# v22_50_maker.net
KiCad netlist of a schematic drawn in EAGLE
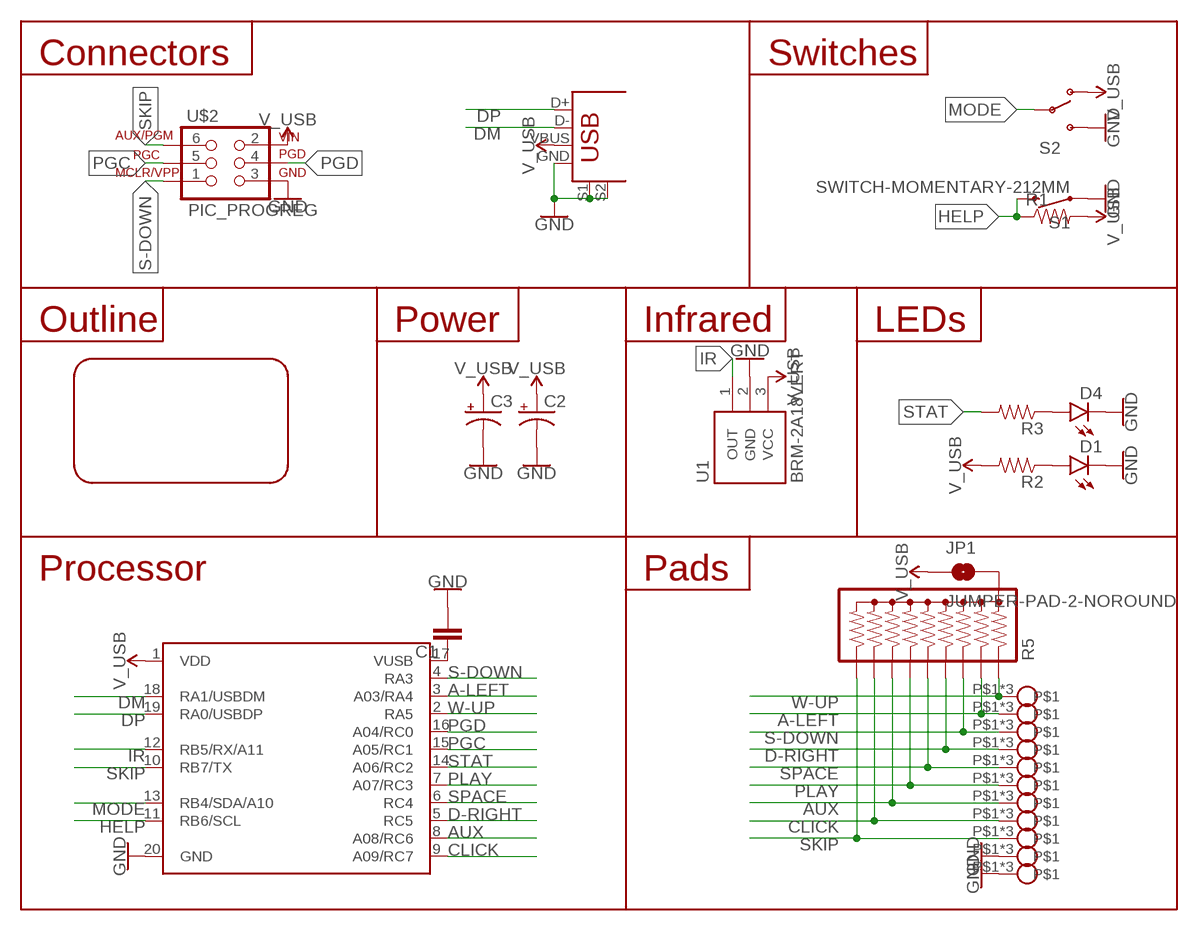
[diagram p0: schematic, sheet 1]

(export (version "E")
  (design (tool "Eeschema 10.0.6"))
  (components
    (comp (ref "C1")
      (value "CAPPTH")
      (footprint "eagle-import:CAP-PTH-SMALL")
      (libsource (lib "eagle-import") (part "CAPPTH"))
    )
    (comp (ref "C2")
      (value "CAP_POLPTH2")
      (footprint "eagle-import:CPOL-RADIAL-10UF-25V")
      (libsource (lib "eagle-import") (part "CAP_POLPTH2"))
    )
    (comp (ref "C3")
      (value "CAP_POLPTH1")
      (footprint "eagle-import:CPOL-RADIAL-100UF-25V")
      (libsource (lib "eagle-import") (part "CAP_POLPTH1"))
    )
    (comp (ref "D1")
      (value "LED3MM")
      (footprint "eagle-import:LED3MM")
      (libsource (lib "eagle-import") (part "LED3MM"))
    )
    (comp (ref "D4")
      (value "LED3MM")
      (footprint "eagle-import:LED3MM")
      (libsource (lib "eagle-import") (part "LED3MM"))
    )
    (comp (ref "JP1")
      (value "JUMPER-PAD-2-NOROUND")
      (footprint "eagle-import:PAD-JUMPER-2-NO_YES_SILK_ROUND")
      (libsource (lib "eagle-import") (part "JUMPER-PAD-2-NOROUND"))
    )
    (comp (ref "R1")
      (value "RESISTORAXIAL-0.3")
      (footprint "eagle-import:AXIAL-0.3")
      (libsource (lib "eagle-import") (part "RESISTORAXIAL-0.3"))
    )
    (comp (ref "R2")
      (value "RESISTORAXIAL-0.3")
      (footprint "eagle-import:AXIAL-0.3")
      (libsource (lib "eagle-import") (part "RESISTORAXIAL-0.3"))
    )
    (comp (ref "R3")
      (value "RESISTORAXIAL-0.3")
      (footprint "eagle-import:AXIAL-0.3")
      (libsource (lib "eagle-import") (part "RESISTORAXIAL-0.3"))
    )
    (comp (ref "R5")
      (value "RPACK-BUSSED-9ROUND")
      (footprint "eagle-import:RPACK-SIP-PTH-9")
      (libsource (lib "eagle-import") (part "RPACK-BUSSED-9ROUND"))
    )
    (comp (ref "S1")
      (value "SWITCH-MOMENTARY-212MM")
      (footprint "eagle-import:TACTILE-PTH-12MM")
      (libsource (lib "eagle-import") (part "SWITCH-MOMENTARY-212MM"))
    )
    (comp (ref "S2")
      (value "SWITCH-SPDTPTH")
      (footprint "eagle-import:SWITCH-SPDT")
      (libsource (lib "eagle-import") (part "SWITCH-SPDTPTH"))
    )
    (comp (ref "U$1")
      (value "PIC16F1459-I/MLDIL")
      (footprint "eagle-import:DIL20")
      (libsource (lib "eagle-import") (part "PIC16F1459-I/MLDIL"))
    )
    (comp (ref "U$2")
      (value "PIC_PROGREG")
      (footprint "eagle-import:1X06")
      (libsource (lib "eagle-import") (part "PIC_PROGREG"))
    )
    (comp (ref "U$3")
      (value "USB+SHIELD")
      (footprint "eagle-import:USB-B-PTH")
      (libsource (lib "eagle-import") (part "USB+SHIELD"))
    )
    (comp (ref "U$4")
      (value "ALLIGATOR")
      (footprint "eagle-import:ALLIGATOR_CLIP_CONNECTOR")
      (libsource (lib "eagle-import") (part "ALLIGATOR"))
    )
    (comp (ref "U$5")
      (value "ALLIGATOR")
      (footprint "eagle-import:ALLIGATOR_CLIP_CONNECTOR")
      (libsource (lib "eagle-import") (part "ALLIGATOR"))
    )
    (comp (ref "U$6")
      (value "ALLIGATOR")
      (footprint "eagle-import:ALLIGATOR_CLIP_CONNECTOR")
      (libsource (lib "eagle-import") (part "ALLIGATOR"))
    )
    (comp (ref "U$7")
      (value "ALLIGATOR")
      (footprint "eagle-import:ALLIGATOR_CLIP_CONNECTOR")
      (libsource (lib "eagle-import") (part "ALLIGATOR"))
    )
    (comp (ref "U$8")
      (value "ALLIGATOR")
      (footprint "eagle-import:ALLIGATOR_CLIP_CONNECTOR")
      (libsource (lib "eagle-import") (part "ALLIGATOR"))
    )
    (comp (ref "U$9")
      (value "ALLIGATOR")
      (footprint "eagle-import:ALLIGATOR_CLIP_CONNECTOR")
      (libsource (lib "eagle-import") (part "ALLIGATOR"))
    )
    (comp (ref "U$10")
      (value "ALLIGATOR")
      (footprint "eagle-import:ALLIGATOR_CLIP_CONNECTOR")
      (libsource (lib "eagle-import") (part "ALLIGATOR"))
    )
    (comp (ref "U$11")
      (value "ALLIGATOR")
      (footprint "eagle-import:ALLIGATOR_CLIP_CONNECTOR")
      (libsource (lib "eagle-import") (part "ALLIGATOR"))
    )
    (comp (ref "U$12")
      (value "ALLIGATOR")
      (footprint "eagle-import:ALLIGATOR_CLIP_CONNECTOR")
      (libsource (lib "eagle-import") (part "ALLIGATOR"))
    )
    (comp (ref "U$13")
      (value "ALLIGATOR")
      (footprint "eagle-import:ALLIGATOR_CLIP_CONNECTOR")
      (libsource (lib "eagle-import") (part "ALLIGATOR"))
    )
    (comp (ref "U$14")
      (value "ALLIGATOR")
      (footprint "eagle-import:ALLIGATOR_CLIP_CONNECTOR")
      (libsource (lib "eagle-import") (part "ALLIGATOR"))
    )
    (comp (ref "U$15")
      (value "CARD_STANDARD50MM")
      (footprint "eagle-import:IEC-7810_ID-1_50MM")
      (libsource (lib "eagle-import") (part "CARD_STANDARD50MM"))
    )
    (comp (ref "U1")
      (value "BRM-2A18VERT")
      (footprint "eagle-import:BRM-2508_VERT")
      (libsource (lib "eagle-import") (part "BRM-2A18VERT"))
    )
  )
  (nets
    (net (code "1") (name "/A-LEFT") (class "Default")
      (node (ref "R5") (pin "P$3") (pinfunction "3_P$3") (pintype "passive"))
      (node (ref "U$1") (pin "3") (pinfunction "A03/RA4_3") (pintype "bidirectional"))
      (node (ref "U$4") (pin "P$1") (pinfunction "P$1_P$1") (pintype "bidirectional"))
      (node (ref "U$4") (pin "P$2") (pinfunction "P$1_P$2") (pintype "bidirectional"))
      (node (ref "U$4") (pin "P$3") (pinfunction "P$1_P$3") (pintype "bidirectional"))
    )
    (net (code "2") (name "/AUX") (class "Default")
      (node (ref "R5") (pin "P$8") (pinfunction "8_P$8") (pintype "passive"))
      (node (ref "U$1") (pin "8") (pinfunction "A08/RC6_8") (pintype "bidirectional"))
      (node (ref "U$10") (pin "P$1") (pinfunction "P$1_P$1") (pintype "bidirectional"))
      (node (ref "U$10") (pin "P$2") (pinfunction "P$1_P$2") (pintype "bidirectional"))
      (node (ref "U$10") (pin "P$3") (pinfunction "P$1_P$3") (pintype "bidirectional"))
    )
    (net (code "3") (name "/CLICK") (class "Default")
      (node (ref "R5") (pin "P$9") (pinfunction "9_P$9") (pintype "passive"))
      (node (ref "U$1") (pin "9") (pinfunction "A09/RC7_9") (pintype "bidirectional"))
      (node (ref "U$11") (pin "P$1") (pinfunction "P$1_P$1") (pintype "bidirectional"))
      (node (ref "U$11") (pin "P$2") (pinfunction "P$1_P$2") (pintype "bidirectional"))
      (node (ref "U$11") (pin "P$3") (pinfunction "P$1_P$3") (pintype "bidirectional"))
    )
    (net (code "4") (name "/D-RIGHT") (class "Default")
      (node (ref "R5") (pin "P$5") (pinfunction "5_P$5") (pintype "passive"))
      (node (ref "U$1") (pin "5") (pinfunction "RC5_5") (pintype "bidirectional"))
      (node (ref "U$5") (pin "P$1") (pinfunction "P$1_P$1") (pintype "bidirectional"))
      (node (ref "U$5") (pin "P$2") (pinfunction "P$1_P$2") (pintype "bidirectional"))
      (node (ref "U$5") (pin "P$3") (pinfunction "P$1_P$3") (pintype "bidirectional"))
    )
    (net (code "5") (name "/DM") (class "Default")
      (node (ref "U$1") (pin "18") (pinfunction "RA1/USBDM_18") (pintype "bidirectional"))
      (node (ref "U$3") (pin "D-") (pinfunction "D-_D-") (pintype "bidirectional"))
    )
    (net (code "6") (name "/DP") (class "Default")
      (node (ref "U$1") (pin "19") (pinfunction "RA0/USBDP_19") (pintype "bidirectional"))
      (node (ref "U$3") (pin "D+") (pinfunction "D+_D+") (pintype "bidirectional"))
    )
    (net (code "7") (name "/PLAY") (class "Default")
      (node (ref "R5") (pin "P$7") (pinfunction "7_P$7") (pintype "passive"))
      (node (ref "U$1") (pin "7") (pinfunction "A07/RC3_7") (pintype "bidirectional"))
      (node (ref "U$9") (pin "P$1") (pinfunction "P$1_P$1") (pintype "bidirectional"))
      (node (ref "U$9") (pin "P$2") (pinfunction "P$1_P$2") (pintype "bidirectional"))
      (node (ref "U$9") (pin "P$3") (pinfunction "P$1_P$3") (pintype "bidirectional"))
    )
    (net (code "8") (name "/SPACE") (class "Default")
      (node (ref "R5") (pin "P$6") (pinfunction "6_P$6") (pintype "passive"))
      (node (ref "U$1") (pin "6") (pinfunction "RC4_6") (pintype "bidirectional"))
      (node (ref "U$8") (pin "P$1") (pinfunction "P$1_P$1") (pintype "bidirectional"))
      (node (ref "U$8") (pin "P$2") (pinfunction "P$1_P$2") (pintype "bidirectional"))
      (node (ref "U$8") (pin "P$3") (pinfunction "P$1_P$3") (pintype "bidirectional"))
    )
    (net (code "9") (name "/W-UP") (class "Default")
      (node (ref "R5") (pin "P$2") (pinfunction "2_P$2") (pintype "passive"))
      (node (ref "U$1") (pin "2") (pinfunction "RA5_2") (pintype "bidirectional"))
      (node (ref "U$6") (pin "P$1") (pinfunction "P$1_P$1") (pintype "bidirectional"))
      (node (ref "U$6") (pin "P$2") (pinfunction "P$1_P$2") (pintype "bidirectional"))
      (node (ref "U$6") (pin "P$3") (pinfunction "P$1_P$3") (pintype "bidirectional"))
    )
    (net (code "10") (name "GND") (class "Default")
      (node (ref "C1") (pin "2") (pinfunction "2_2") (pintype "passive"))
      (node (ref "C2") (pin "2") (pinfunction "-_2") (pintype "passive"))
      (node (ref "C3") (pin "2") (pinfunction "-_2") (pintype "passive"))
      (node (ref "D1") (pin "K") (pinfunction "C_K") (pintype "passive"))
      (node (ref "D4") (pin "K") (pinfunction "C_K") (pintype "passive"))
      (node (ref "S1") (pin "1") (pinfunction "1_1") (pintype "passive"))
      (node (ref "S1") (pin "2") (pinfunction "1_2") (pintype "passive"))
      (node (ref "S2") (pin "3") (pinfunction "S_3") (pintype "passive"))
      (node (ref "U$1") (pin "20") (pinfunction "GND_20") (pintype "bidirectional"))
      (node (ref "U$13") (pin "P$1") (pinfunction "P$1_P$1") (pintype "bidirectional"))
      (node (ref "U$13") (pin "P$2") (pinfunction "P$1_P$2") (pintype "bidirectional"))
      (node (ref "U$13") (pin "P$3") (pinfunction "P$1_P$3") (pintype "bidirectional"))
      (node (ref "U$14") (pin "P$1") (pinfunction "P$1_P$1") (pintype "bidirectional"))
      (node (ref "U$14") (pin "P$2") (pinfunction "P$1_P$2") (pintype "bidirectional"))
      (node (ref "U$14") (pin "P$3") (pinfunction "P$1_P$3") (pintype "bidirectional"))
      (node (ref "U$2") (pin "3") (pinfunction "GND_3") (pintype "passive"))
      (node (ref "U$3") (pin "GND") (pinfunction "GND_GND") (pintype "bidirectional"))
      (node (ref "U$3") (pin "S1") (pinfunction "S1_S1") (pintype "bidirectional"))
      (node (ref "U$3") (pin "S2") (pinfunction "S2_S2") (pintype "bidirectional"))
      (node (ref "U1") (pin "2") (pinfunction "GND_2") (pintype "bidirectional"))
    )
    (net (code "11") (name "HELP") (class "Default")
      (node (ref "R1") (pin "P$1") (pinfunction "1_P$1") (pintype "passive"))
      (node (ref "S1") (pin "3") (pinfunction "2_3") (pintype "passive"))
      (node (ref "S1") (pin "4") (pinfunction "2_4") (pintype "passive"))
      (node (ref "U$1") (pin "11") (pinfunction "RB6/SCL_11") (pintype "bidirectional"))
    )
    (net (code "12") (name "IR") (class "Default")
      (node (ref "U$1") (pin "12") (pinfunction "RB5/RX/A11_12") (pintype "bidirectional"))
      (node (ref "U1") (pin "1") (pinfunction "OUT_1") (pintype "bidirectional"))
    )
    (net (code "13") (name "MODE") (class "Default")
      (node (ref "S2") (pin "2") (pinfunction "P_2") (pintype "passive"))
      (node (ref "U$1") (pin "13") (pinfunction "RB4/SDA/A10_13") (pintype "bidirectional"))
    )
    (net (code "14") (name "Net-(R2-1)") (class "Default")
      (node (ref "D1") (pin "A") (pinfunction "A_A") (pintype "passive"))
      (node (ref "R2") (pin "P$1") (pinfunction "1_P$1") (pintype "passive"))
    )
    (net (code "15") (name "Net-(R3-1)") (class "Default")
      (node (ref "D4") (pin "A") (pinfunction "A_A") (pintype "passive"))
      (node (ref "R3") (pin "P$1") (pinfunction "1_P$1") (pintype "passive"))
    )
    (net (code "16") (name "Net-(R5-1)") (class "Default")
      (node (ref "JP1") (pin "2") (pinfunction "2_2") (pintype "passive"))
      (node (ref "R5") (pin "P$1") (pinfunction "1_P$1") (pintype "passive"))
    )
    (net (code "17") (name "Net-(U$1-VUSB)") (class "Default")
      (node (ref "C1") (pin "1") (pinfunction "1_1") (pintype "passive"))
      (node (ref "U$1") (pin "17") (pinfunction "VUSB_17") (pintype "bidirectional"))
    )
    (net (code "18") (name "PGC") (class "Default")
      (node (ref "U$1") (pin "15") (pinfunction "A05/RC1_15") (pintype "bidirectional"))
      (node (ref "U$2") (pin "5") (pinfunction "PGC_5") (pintype "passive"))
    )
    (net (code "19") (name "PGD") (class "Default")
      (node (ref "U$1") (pin "16") (pinfunction "A04/RC0_16") (pintype "bidirectional"))
      (node (ref "U$2") (pin "4") (pinfunction "PGD_4") (pintype "passive"))
    )
    (net (code "20") (name "S-DOWN") (class "Default")
      (node (ref "R5") (pin "P$4") (pinfunction "4_P$4") (pintype "passive"))
      (node (ref "U$1") (pin "4") (pinfunction "RA3_4") (pintype "bidirectional"))
      (node (ref "U$2") (pin "1") (pinfunction "MCLR/VPP_1") (pintype "passive"))
      (node (ref "U$7") (pin "P$1") (pinfunction "P$1_P$1") (pintype "bidirectional"))
      (node (ref "U$7") (pin "P$2") (pinfunction "P$1_P$2") (pintype "bidirectional"))
      (node (ref "U$7") (pin "P$3") (pinfunction "P$1_P$3") (pintype "bidirectional"))
    )
    (net (code "21") (name "SKIP") (class "Default")
      (node (ref "R5") (pin "P$10") (pinfunction "10_P$10") (pintype "passive"))
      (node (ref "U$1") (pin "10") (pinfunction "RB7/TX_10") (pintype "bidirectional"))
      (node (ref "U$12") (pin "P$1") (pinfunction "P$1_P$1") (pintype "bidirectional"))
      (node (ref "U$12") (pin "P$2") (pinfunction "P$1_P$2") (pintype "bidirectional"))
      (node (ref "U$12") (pin "P$3") (pinfunction "P$1_P$3") (pintype "bidirectional"))
      (node (ref "U$2") (pin "6") (pinfunction "AUX/PGM_6") (pintype "passive"))
    )
    (net (code "22") (name "STAT") (class "Default")
      (node (ref "R3") (pin "P$2") (pinfunction "2_P$2") (pintype "passive"))
      (node (ref "U$1") (pin "14") (pinfunction "A06/RC2_14") (pintype "bidirectional"))
    )
    (net (code "23") (name "V_USB") (class "Default")
      (node (ref "C2") (pin "1") (pinfunction "+_1") (pintype "passive"))
      (node (ref "C3") (pin "1") (pinfunction "+_1") (pintype "passive"))
      (node (ref "JP1") (pin "1") (pinfunction "1_1") (pintype "passive"))
      (node (ref "R1") (pin "P$2") (pinfunction "2_P$2") (pintype "passive"))
      (node (ref "R2") (pin "P$2") (pinfunction "2_P$2") (pintype "passive"))
      (node (ref "S2") (pin "1") (pinfunction "O_1") (pintype "passive"))
      (node (ref "U$1") (pin "1") (pinfunction "VDD_1") (pintype "bidirectional"))
      (node (ref "U$2") (pin "2") (pinfunction "VIN_2") (pintype "passive"))
      (node (ref "U$3") (pin "VBUS") (pinfunction "VBUS_VBUS") (pintype "bidirectional"))
      (node (ref "U1") (pin "3") (pinfunction "VCC_3") (pintype "bidirectional"))
    )
  )
)
